# Quadcopter_shield.net
KiCad netlist of a schematic drawn in EAGLE
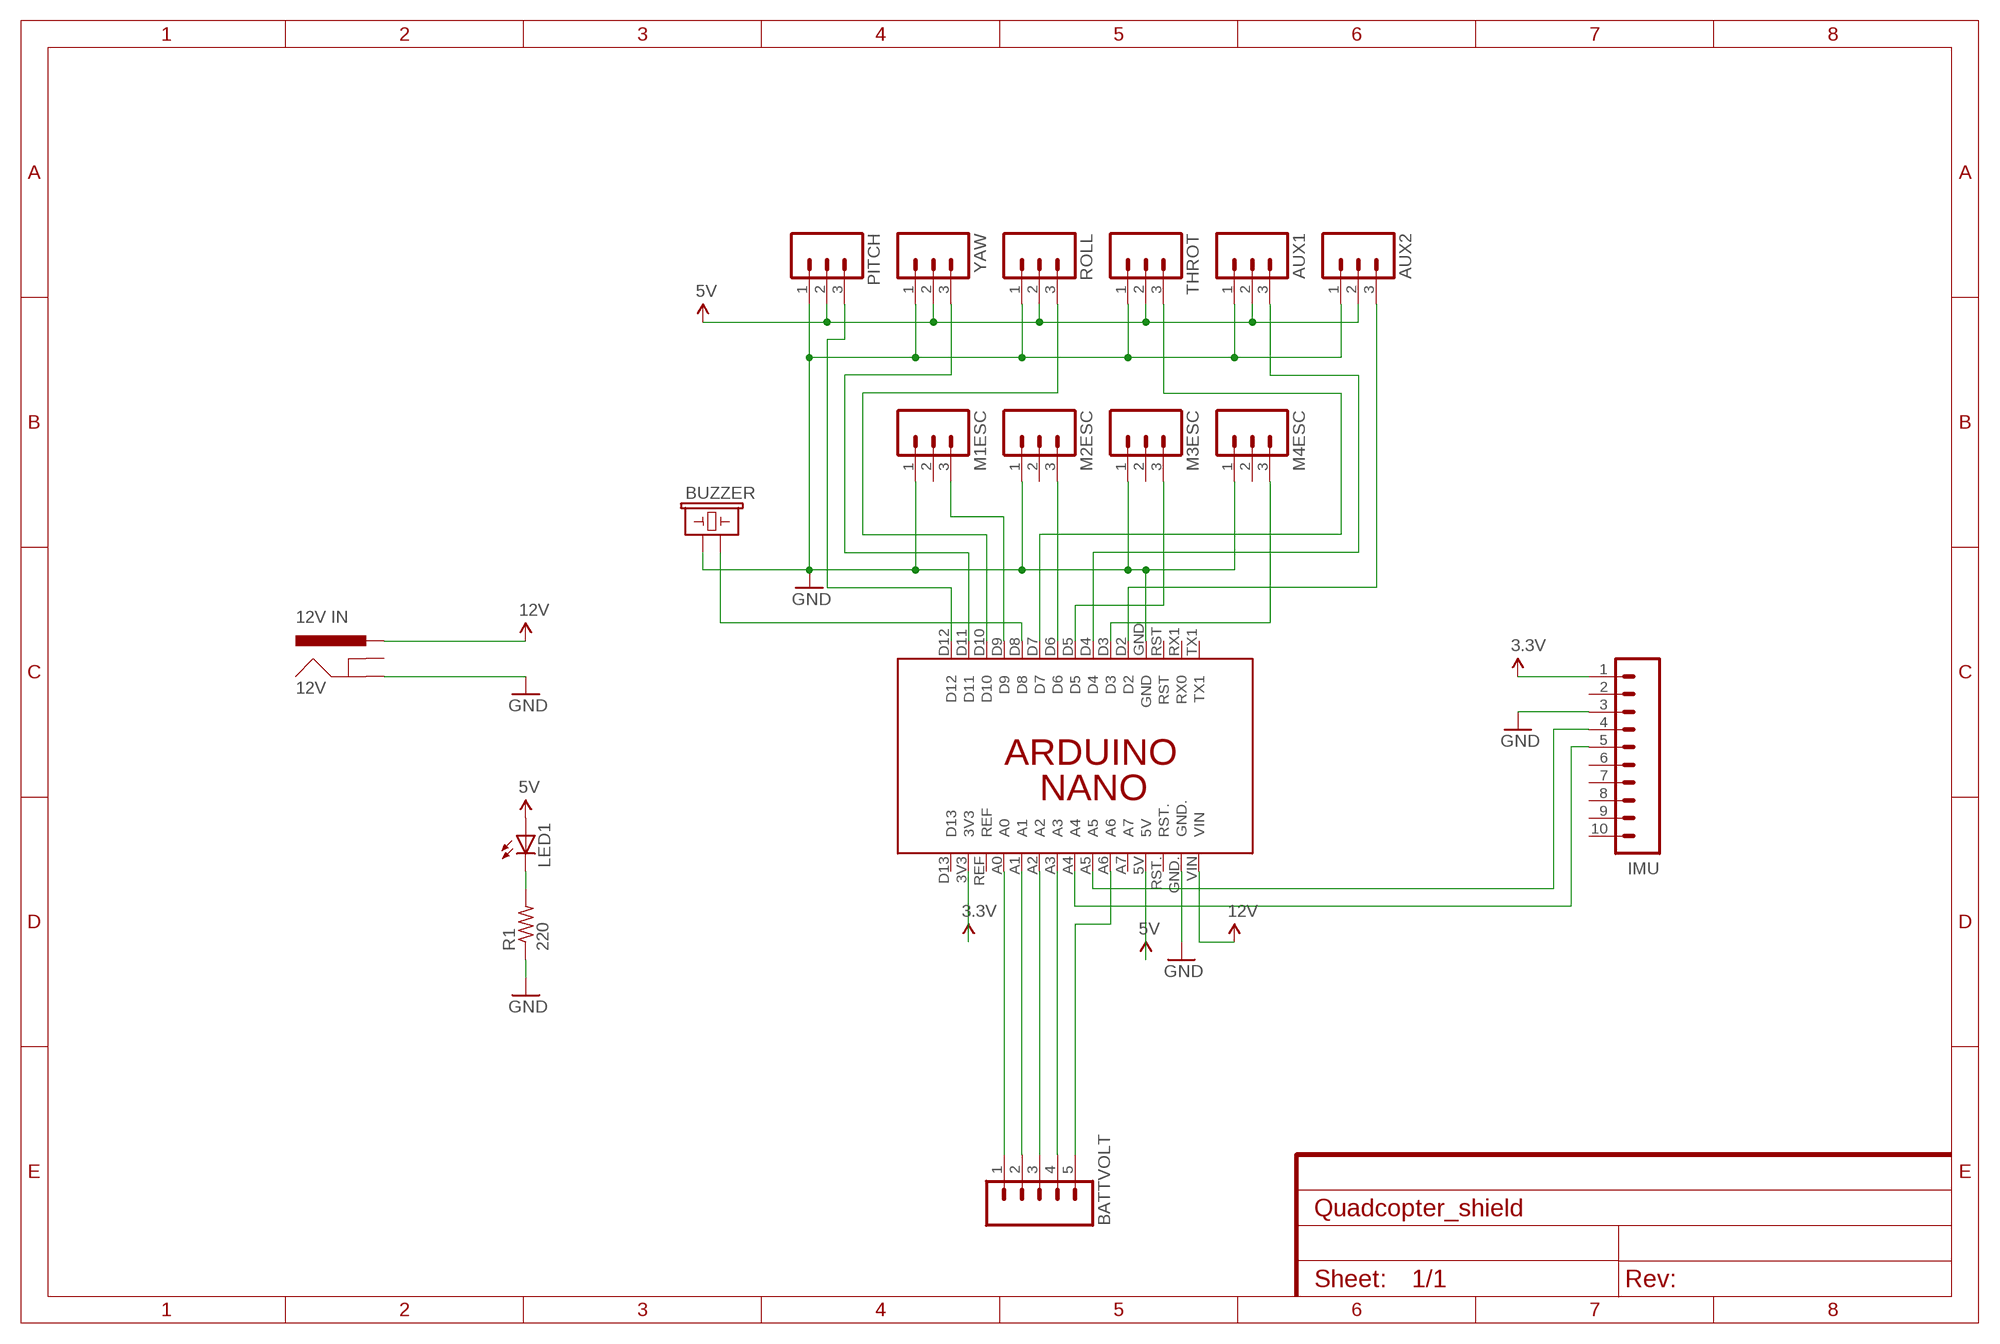
[diagram p0: schematic, sheet 1]

(export (version "E")
  (design (tool "Eeschema 10.0.6"))
  (components
    (comp (ref "12V")
      (value "12V IN")
      (footprint "eagle-import:POWER_JACK_PTH_LOCK")
      (libsource (lib "eagle-import") (part "POWER_JACKPTH_LOCK"))
    )
    (comp (ref "AUX1")
      (value "M03PTH")
      (footprint "eagle-import:1X03")
      (libsource (lib "eagle-import") (part "M03PTH"))
    )
    (comp (ref "AUX2")
      (value "M03PTH")
      (footprint "eagle-import:1X03")
      (libsource (lib "eagle-import") (part "M03PTH"))
    )
    (comp (ref "BATTVOLT")
      (value "M05PTH")
      (footprint "eagle-import:1X05")
      (libsource (lib "eagle-import") (part "M05PTH"))
    )
    (comp (ref "BUZZER")
      (value "BUZZERNS")
      (footprint "eagle-import:BUZZER-12MM-NS")
      (libsource (lib "eagle-import") (part "BUZZERNS"))
    )
    (comp (ref "IMU")
      (value "M10SILK_FEMALE_PTH")
      (footprint "eagle-import:1X10")
      (libsource (lib "eagle-import") (part "M10SILK_FEMALE_PTH"))
    )
    (comp (ref "LED1")
      (value "TLLR4400")
      (footprint "eagle-import:LED3MM")
      (fields (field (name "MF") "VISHAY SEMICONDUCTOR"))
      (libsource (lib "eagle-import") (part "TLLR4400"))
    )
    (comp (ref "M1ESC")
      (value "M03PTH")
      (footprint "eagle-import:1X03")
      (libsource (lib "eagle-import") (part "M03PTH"))
    )
    (comp (ref "M2ESC")
      (value "M03PTH")
      (footprint "eagle-import:1X03")
      (libsource (lib "eagle-import") (part "M03PTH"))
    )
    (comp (ref "M3ESC")
      (value "M03PTH")
      (footprint "eagle-import:1X03")
      (libsource (lib "eagle-import") (part "M03PTH"))
    )
    (comp (ref "M4ESC")
      (value "M03PTH")
      (footprint "eagle-import:1X03")
      (libsource (lib "eagle-import") (part "M03PTH"))
    )
    (comp (ref "PCB1")
      (value "ARDUINO_NANO")
      (footprint "eagle-import:ARDUINO_NANO")
      (libsource (lib "eagle-import") (part "ARDUINO_NANO"))
    )
    (comp (ref "PITCH")
      (value "M03PTH")
      (footprint "eagle-import:1X03")
      (libsource (lib "eagle-import") (part "M03PTH"))
    )
    (comp (ref "R1")
      (value "220")
      (footprint "eagle-import:0411V")
      (libsource (lib "eagle-import") (part "R-US_0411/3V"))
    )
    (comp (ref "ROLL")
      (value "M03PTH")
      (footprint "eagle-import:1X03")
      (libsource (lib "eagle-import") (part "M03PTH"))
    )
    (comp (ref "THROT")
      (value "M03PTH")
      (footprint "eagle-import:1X03")
      (libsource (lib "eagle-import") (part "M03PTH"))
    )
    (comp (ref "YAW")
      (value "M03PTH")
      (footprint "eagle-import:1X03")
      (libsource (lib "eagle-import") (part "M03PTH"))
    )
  )
  (nets
    (net (code "1") (name "3.3V") (class "Default")
      (node (ref "IMU") (pin "1") (pinfunction "1_1") (pintype "passive"))
      (node (ref "PCB1") (pin "3V3") (pinfunction "3V3_3V3") (pintype "bidirectional"))
    )
    (net (code "2") (name "5V") (class "Default")
      (node (ref "AUX1") (pin "2") (pinfunction "2_2") (pintype "passive"))
      (node (ref "AUX2") (pin "2") (pinfunction "2_2") (pintype "passive"))
      (node (ref "LED1") (pin "A") (pinfunction "A_A") (pintype "passive"))
      (node (ref "PCB1") (pin "5V") (pinfunction "5V_5V") (pintype "bidirectional"))
      (node (ref "PITCH") (pin "2") (pinfunction "2_2") (pintype "passive"))
      (node (ref "ROLL") (pin "2") (pinfunction "2_2") (pintype "passive"))
      (node (ref "THROT") (pin "2") (pinfunction "2_2") (pintype "passive"))
      (node (ref "YAW") (pin "2") (pinfunction "2_2") (pintype "passive"))
    )
    (net (code "3") (name "12V") (class "Default")
      (node (ref "12V") (pin "PWR") (pinfunction "PWR_PWR") (pintype "bidirectional"))
      (node (ref "PCB1") (pin "VIN") (pinfunction "VIN_VIN") (pintype "bidirectional"))
    )
    (net (code "4") (name "GND") (class "Default")
      (node (ref "12V") (pin "GND") (pinfunction "GND_GND") (pintype "bidirectional"))
      (node (ref "AUX1") (pin "1") (pinfunction "1_1") (pintype "passive"))
      (node (ref "AUX2") (pin "1") (pinfunction "1_1") (pintype "passive"))
      (node (ref "BUZZER") (pin "+") (pinfunction "1_+") (pintype "passive"))
      (node (ref "IMU") (pin "3") (pinfunction "3_3") (pintype "passive"))
      (node (ref "M1ESC") (pin "1") (pinfunction "1_1") (pintype "passive"))
      (node (ref "M2ESC") (pin "1") (pinfunction "1_1") (pintype "passive"))
      (node (ref "M3ESC") (pin "1") (pinfunction "1_1") (pintype "passive"))
      (node (ref "M4ESC") (pin "1") (pinfunction "1_1") (pintype "passive"))
      (node (ref "PCB1") (pin "GND") (pinfunction "GND_GND") (pintype "bidirectional"))
      (node (ref "PCB1") (pin "GND.") (pinfunction "GND._GND.") (pintype "bidirectional"))
      (node (ref "PITCH") (pin "1") (pinfunction "1_1") (pintype "passive"))
      (node (ref "R1") (pin "1") (pinfunction "1_1") (pintype "passive"))
      (node (ref "ROLL") (pin "1") (pinfunction "1_1") (pintype "passive"))
      (node (ref "THROT") (pin "1") (pinfunction "1_1") (pintype "passive"))
      (node (ref "YAW") (pin "1") (pinfunction "1_1") (pintype "passive"))
    )
    (net (code "5") (name "Net-(AUX1-Pad3)") (class "Default")
      (node (ref "AUX1") (pin "3") (pinfunction "3_3") (pintype "passive"))
      (node (ref "PCB1") (pin "D4") (pinfunction "D4_D4") (pintype "bidirectional"))
    )
    (net (code "6") (name "Net-(AUX2-Pad3)") (class "Default")
      (node (ref "AUX2") (pin "3") (pinfunction "3_3") (pintype "passive"))
      (node (ref "PCB1") (pin "D2") (pinfunction "D2_D2") (pintype "bidirectional"))
    )
    (net (code "7") (name "Net-(BATTVOLT-Pad1)") (class "Default")
      (node (ref "BATTVOLT") (pin "1") (pinfunction "1_1") (pintype "passive"))
      (node (ref "PCB1") (pin "A0") (pinfunction "A0_A0") (pintype "bidirectional"))
    )
    (net (code "8") (name "Net-(BATTVOLT-Pad2)") (class "Default")
      (node (ref "BATTVOLT") (pin "2") (pinfunction "2_2") (pintype "passive"))
      (node (ref "PCB1") (pin "A1") (pinfunction "A1_A1") (pintype "bidirectional"))
    )
    (net (code "9") (name "Net-(BATTVOLT-Pad3)") (class "Default")
      (node (ref "BATTVOLT") (pin "3") (pinfunction "3_3") (pintype "passive"))
      (node (ref "PCB1") (pin "A2") (pinfunction "A2_A2") (pintype "bidirectional"))
    )
    (net (code "10") (name "Net-(BATTVOLT-Pad4)") (class "Default")
      (node (ref "BATTVOLT") (pin "4") (pinfunction "4_4") (pintype "passive"))
      (node (ref "PCB1") (pin "A3") (pinfunction "A3_A3") (pintype "bidirectional"))
    )
    (net (code "11") (name "Net-(BATTVOLT-Pad5)") (class "Default")
      (node (ref "BATTVOLT") (pin "5") (pinfunction "5_5") (pintype "passive"))
      (node (ref "PCB1") (pin "A6") (pinfunction "A6_A6") (pintype "bidirectional"))
    )
    (net (code "12") (name "Net-(BUZZER-2)") (class "Default")
      (node (ref "BUZZER") (pin "-") (pinfunction "2_-") (pintype "passive"))
      (node (ref "PCB1") (pin "D8") (pinfunction "D8_D8") (pintype "bidirectional"))
    )
    (net (code "13") (name "Net-(IMU-Pad4)") (class "Default")
      (node (ref "IMU") (pin "4") (pinfunction "4_4") (pintype "passive"))
      (node (ref "PCB1") (pin "A5") (pinfunction "A5_A5") (pintype "bidirectional"))
    )
    (net (code "14") (name "Net-(IMU-Pad5)") (class "Default")
      (node (ref "IMU") (pin "5") (pinfunction "5_5") (pintype "passive"))
      (node (ref "PCB1") (pin "A4") (pinfunction "A4_A4") (pintype "bidirectional"))
    )
    (net (code "15") (name "Net-(LED1-C)") (class "Default")
      (node (ref "LED1") (pin "K") (pinfunction "C_K") (pintype "passive"))
      (node (ref "R1") (pin "2") (pinfunction "2_2") (pintype "passive"))
    )
    (net (code "16") (name "Net-(M1ESC-Pad3)") (class "Default")
      (node (ref "M1ESC") (pin "3") (pinfunction "3_3") (pintype "passive"))
      (node (ref "PCB1") (pin "D9") (pinfunction "D9_D9") (pintype "bidirectional"))
    )
    (net (code "17") (name "Net-(M2ESC-Pad3)") (class "Default")
      (node (ref "M2ESC") (pin "3") (pinfunction "3_3") (pintype "passive"))
      (node (ref "PCB1") (pin "D6") (pinfunction "D6_D6") (pintype "bidirectional"))
    )
    (net (code "18") (name "Net-(M3ESC-Pad3)") (class "Default")
      (node (ref "M3ESC") (pin "3") (pinfunction "3_3") (pintype "passive"))
      (node (ref "PCB1") (pin "D5") (pinfunction "D5_D5") (pintype "bidirectional"))
    )
    (net (code "19") (name "Net-(M4ESC-Pad3)") (class "Default")
      (node (ref "M4ESC") (pin "3") (pinfunction "3_3") (pintype "passive"))
      (node (ref "PCB1") (pin "D3") (pinfunction "D3_D3") (pintype "bidirectional"))
    )
    (net (code "20") (name "Net-(PCB1-PadD7)") (class "Default")
      (node (ref "PCB1") (pin "D7") (pinfunction "D7_D7") (pintype "bidirectional"))
      (node (ref "THROT") (pin "3") (pinfunction "3_3") (pintype "passive"))
    )
    (net (code "21") (name "Net-(PCB1-PadD10)") (class "Default")
      (node (ref "PCB1") (pin "D10") (pinfunction "D10_D10") (pintype "bidirectional"))
      (node (ref "ROLL") (pin "3") (pinfunction "3_3") (pintype "passive"))
    )
    (net (code "22") (name "Net-(PCB1-PadD11)") (class "Default")
      (node (ref "PCB1") (pin "D11") (pinfunction "D11_D11") (pintype "bidirectional"))
      (node (ref "YAW") (pin "3") (pinfunction "3_3") (pintype "passive"))
    )
    (net (code "23") (name "Net-(PCB1-PadD12)") (class "Default")
      (node (ref "PCB1") (pin "D12") (pinfunction "D12_D12") (pintype "bidirectional"))
      (node (ref "PITCH") (pin "3") (pinfunction "3_3") (pintype "passive"))
    )
    (net (code "24") (name "unconnected-(12V-PadGNDBREAK)") (class "Default")
      (node (ref "12V") (pin "GNDBREAK") (pinfunction "GNDBREAK_GNDBREAK") (pintype "bidirectional"))
    )
    (net (code "25") (name "unconnected-(IMU-Pad2)") (class "Default")
      (node (ref "IMU") (pin "2") (pinfunction "2_2") (pintype "passive"))
    )
    (net (code "26") (name "unconnected-(IMU-Pad6)") (class "Default")
      (node (ref "IMU") (pin "6") (pinfunction "6_6") (pintype "passive"))
    )
    (net (code "27") (name "unconnected-(IMU-Pad7)") (class "Default")
      (node (ref "IMU") (pin "7") (pinfunction "7_7") (pintype "passive"))
    )
    (net (code "28") (name "unconnected-(IMU-Pad8)") (class "Default")
      (node (ref "IMU") (pin "8") (pinfunction "8_8") (pintype "passive"))
    )
    (net (code "29") (name "unconnected-(IMU-Pad9)") (class "Default")
      (node (ref "IMU") (pin "9") (pinfunction "9_9") (pintype "passive"))
    )
    (net (code "30") (name "unconnected-(IMU-Pad10)") (class "Default")
      (node (ref "IMU") (pin "10") (pinfunction "10_10") (pintype "passive"))
    )
    (net (code "31") (name "unconnected-(M1ESC-Pad2)") (class "Default")
      (node (ref "M1ESC") (pin "2") (pinfunction "2_2") (pintype "passive"))
    )
    (net (code "32") (name "unconnected-(M2ESC-Pad2)") (class "Default")
      (node (ref "M2ESC") (pin "2") (pinfunction "2_2") (pintype "passive"))
    )
    (net (code "33") (name "unconnected-(M3ESC-Pad2)") (class "Default")
      (node (ref "M3ESC") (pin "2") (pinfunction "2_2") (pintype "passive"))
    )
    (net (code "34") (name "unconnected-(M4ESC-Pad2)") (class "Default")
      (node (ref "M4ESC") (pin "2") (pinfunction "2_2") (pintype "passive"))
    )
    (net (code "35") (name "unconnected-(PCB1-PadA7)") (class "Default")
      (node (ref "PCB1") (pin "A7") (pinfunction "A7_A7") (pintype "bidirectional"))
    )
    (net (code "36") (name "unconnected-(PCB1-PadD13)") (class "Default")
      (node (ref "PCB1") (pin "D13") (pinfunction "D13_D13") (pintype "bidirectional"))
    )
    (net (code "37") (name "unconnected-(PCB1-PadREF)") (class "Default")
      (node (ref "PCB1") (pin "REF") (pinfunction "REF_REF") (pintype "bidirectional"))
    )
    (net (code "38") (name "unconnected-(PCB1-PadRST)") (class "Default")
      (node (ref "PCB1") (pin "RST") (pinfunction "RST_RST") (pintype "bidirectional"))
    )
    (net (code "39") (name "unconnected-(PCB1-PadRST.)") (class "Default")
      (node (ref "PCB1") (pin "RST.") (pinfunction "RST._RST.") (pintype "bidirectional"))
    )
    (net (code "40") (name "unconnected-(PCB1-PadTX1)") (class "Default")
      (node (ref "PCB1") (pin "TX1") (pinfunction "TX1_TX1") (pintype "bidirectional"))
    )
    (net (code "41") (name "unconnected-(PCB1-RX0-PadRX1)") (class "Default")
      (node (ref "PCB1") (pin "RX1") (pinfunction "RX0_RX1") (pintype "bidirectional"))
    )
  )
)
